# sd_adapter.net
KiCad netlist of a schematic drawn in EAGLE
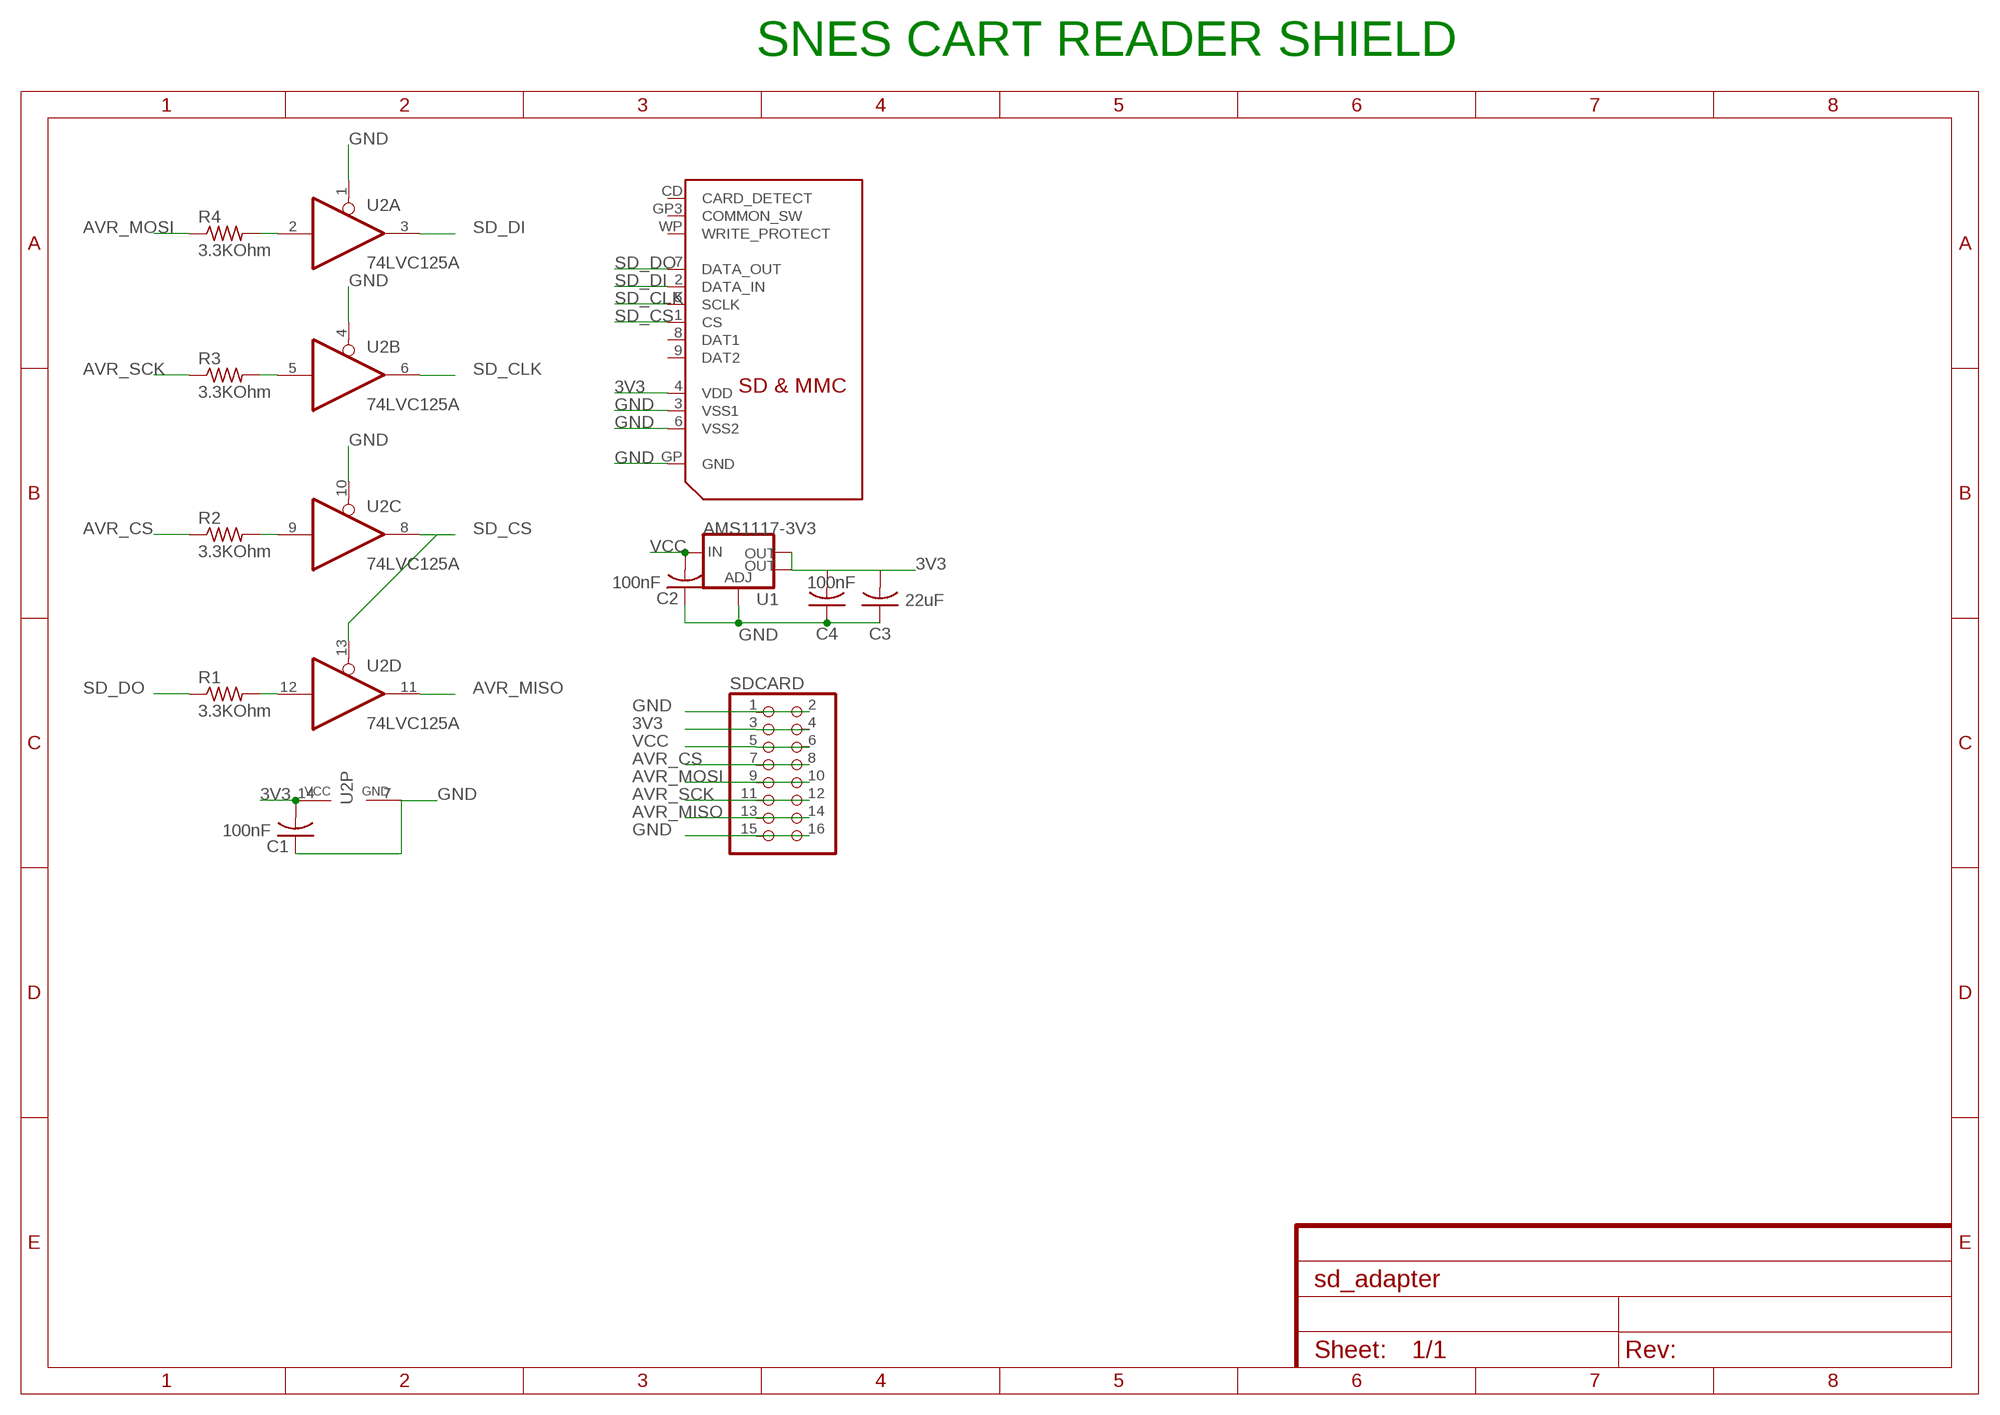
[diagram p0: schematic, sheet 1]

(export (version "E")
  (design (tool "Eeschema 10.0.6"))
  (components
    (comp (ref "C1")
      (value "100nF")
      (footprint "eagle-import:C0805")
      (libsource (lib "eagle-import") (part "C-USC0805"))
    )
    (comp (ref "C2")
      (value "100nF")
      (footprint "eagle-import:C0805")
      (libsource (lib "eagle-import") (part "C-USC0805"))
    )
    (comp (ref "C3")
      (value "22uF")
      (footprint "eagle-import:C0805")
      (libsource (lib "eagle-import") (part "C-USC0805"))
    )
    (comp (ref "C4")
      (value "100nF")
      (footprint "eagle-import:C0805")
      (libsource (lib "eagle-import") (part "C-USC0805"))
    )
    (comp (ref "R1")
      (value "3.3KOhm")
      (footprint "eagle-import:R0805")
      (libsource (lib "eagle-import") (part "R-US_R0805"))
    )
    (comp (ref "R2")
      (value "3.3KOhm")
      (footprint "eagle-import:R0805")
      (libsource (lib "eagle-import") (part "R-US_R0805"))
    )
    (comp (ref "R3")
      (value "3.3KOhm")
      (footprint "eagle-import:R0805")
      (libsource (lib "eagle-import") (part "R-US_R0805"))
    )
    (comp (ref "R4")
      (value "3.3KOhm")
      (footprint "eagle-import:R0805")
      (libsource (lib "eagle-import") (part "R-US_R0805"))
    )
    (comp (ref "SDCARD")
      (value "PINHD-2X8_2.54")
      (footprint "eagle-import:2X08")
      (libsource (lib "eagle-import") (part "PINHD-2X8_2.54"))
    )
    (comp (ref "U$1")
      (value "SDMMC06132")
      (footprint "eagle-import:06132")
      (libsource (lib "eagle-import") (part "SDMMC06132"))
    )
    (comp (ref "U1")
      (value "AMS1117-3V3")
      (footprint "eagle-import:SOT223")
      (libsource (lib "eagle-import") (part "SMD-AMS1117SOT223"))
    )
    (comp (ref "U2")
      (value "74LVC125A")
      (footprint "eagle-import:TSSOP14")
      (libsource (lib "eagle-import") (part "74125PWABT"))
    )
  )
  (nets
    (net (code "1") (name "/3V3") (class "Default")
      (node (ref "C1") (pin "2") (pinfunction "2_2") (pintype "passive"))
      (node (ref "C3") (pin "2") (pinfunction "2_2") (pintype "passive"))
      (node (ref "C4") (pin "2") (pinfunction "2_2") (pintype "passive"))
      (node (ref "SDCARD") (pin "3") (pinfunction "3_3") (pintype "passive"))
      (node (ref "SDCARD") (pin "4") (pinfunction "4_4") (pintype "passive"))
      (node (ref "U$1") (pin "4") (pinfunction "VDD_4") (pintype "power_in"))
      (node (ref "U1") (pin "2") (pinfunction "OUT_2") (pintype "output"))
      (node (ref "U1") (pin "4") (pinfunction "OUT_4") (pintype "output"))
      (node (ref "U2") (pin "14") (pinfunction "VCC_14") (pintype "power_in"))
    )
    (net (code "2") (name "/AVR_CS") (class "Default")
      (node (ref "R2") (pin "1") (pinfunction "1_1") (pintype "passive"))
      (node (ref "SDCARD") (pin "7") (pinfunction "7_7") (pintype "passive"))
      (node (ref "SDCARD") (pin "8") (pinfunction "8_8") (pintype "passive"))
    )
    (net (code "3") (name "/AVR_MISO") (class "Default")
      (node (ref "SDCARD") (pin "13") (pinfunction "13_13") (pintype "passive"))
      (node (ref "SDCARD") (pin "14") (pinfunction "14_14") (pintype "passive"))
      (node (ref "U2") (pin "11") (pinfunction "O_11") (pintype "tri_state"))
    )
    (net (code "4") (name "/AVR_MOSI") (class "Default")
      (node (ref "R4") (pin "1") (pinfunction "1_1") (pintype "passive"))
      (node (ref "SDCARD") (pin "10") (pinfunction "10_10") (pintype "passive"))
      (node (ref "SDCARD") (pin "9") (pinfunction "9_9") (pintype "passive"))
    )
    (net (code "5") (name "/AVR_SCK") (class "Default")
      (node (ref "R3") (pin "1") (pinfunction "1_1") (pintype "passive"))
      (node (ref "SDCARD") (pin "11") (pinfunction "11_11") (pintype "passive"))
      (node (ref "SDCARD") (pin "12") (pinfunction "12_12") (pintype "passive"))
    )
    (net (code "6") (name "/GND") (class "Default")
      (node (ref "C1") (pin "1") (pinfunction "1_1") (pintype "passive"))
      (node (ref "C2") (pin "1") (pinfunction "1_1") (pintype "passive"))
      (node (ref "C3") (pin "1") (pinfunction "1_1") (pintype "passive"))
      (node (ref "C4") (pin "1") (pinfunction "1_1") (pintype "passive"))
      (node (ref "SDCARD") (pin "1") (pinfunction "1_1") (pintype "passive"))
      (node (ref "SDCARD") (pin "15") (pinfunction "15_15") (pintype "passive"))
      (node (ref "SDCARD") (pin "16") (pinfunction "16_16") (pintype "passive"))
      (node (ref "SDCARD") (pin "2") (pinfunction "2_2") (pintype "passive"))
      (node (ref "U$1") (pin "3") (pinfunction "VSS1_3") (pintype "power_in"))
      (node (ref "U$1") (pin "6") (pinfunction "VSS2_6") (pintype "power_in"))
      (node (ref "U$1") (pin "GP") (pinfunction "GND_GP") (pintype "power_in"))
      (node (ref "U1") (pin "1") (pinfunction "ADJ_1") (pintype "input"))
      (node (ref "U2") (pin "1") (pinfunction "OE_1") (pintype "input"))
      (node (ref "U2") (pin "10") (pinfunction "OE_10") (pintype "input"))
      (node (ref "U2") (pin "4") (pinfunction "OE_4") (pintype "input"))
      (node (ref "U2") (pin "7") (pinfunction "GND_7") (pintype "power_in"))
    )
    (net (code "7") (name "/SD_CLK") (class "Default")
      (node (ref "U$1") (pin "5") (pinfunction "SCLK_5") (pintype "input"))
      (node (ref "U2") (pin "6") (pinfunction "O_6") (pintype "tri_state"))
    )
    (net (code "8") (name "/SD_CS") (class "Default")
      (node (ref "U$1") (pin "1") (pinfunction "CS_1") (pintype "input"))
      (node (ref "U2") (pin "13") (pinfunction "OE_13") (pintype "input"))
      (node (ref "U2") (pin "8") (pinfunction "O_8") (pintype "tri_state"))
    )
    (net (code "9") (name "/SD_DI") (class "Default")
      (node (ref "U$1") (pin "2") (pinfunction "DATA_IN_2") (pintype "input"))
      (node (ref "U2") (pin "3") (pinfunction "O_3") (pintype "tri_state"))
    )
    (net (code "10") (name "/SD_DO") (class "Default")
      (node (ref "R1") (pin "1") (pinfunction "1_1") (pintype "passive"))
      (node (ref "U$1") (pin "7") (pinfunction "DATA_OUT_7") (pintype "output"))
    )
    (net (code "11") (name "/VCC") (class "Default")
      (node (ref "C2") (pin "2") (pinfunction "2_2") (pintype "passive"))
      (node (ref "SDCARD") (pin "5") (pinfunction "5_5") (pintype "passive"))
      (node (ref "SDCARD") (pin "6") (pinfunction "6_6") (pintype "passive"))
      (node (ref "U1") (pin "3") (pinfunction "IN_3") (pintype "input"))
    )
    (net (code "12") (name "Net-(U2A-I)") (class "Default")
      (node (ref "R4") (pin "2") (pinfunction "2_2") (pintype "passive"))
      (node (ref "U2") (pin "2") (pinfunction "I_2") (pintype "input"))
    )
    (net (code "13") (name "Net-(U2B-I)") (class "Default")
      (node (ref "R3") (pin "2") (pinfunction "2_2") (pintype "passive"))
      (node (ref "U2") (pin "5") (pinfunction "I_5") (pintype "input"))
    )
    (net (code "14") (name "Net-(U2C-I)") (class "Default")
      (node (ref "R2") (pin "2") (pinfunction "2_2") (pintype "passive"))
      (node (ref "U2") (pin "9") (pinfunction "I_9") (pintype "input"))
    )
    (net (code "15") (name "Net-(U2D-I)") (class "Default")
      (node (ref "R1") (pin "2") (pinfunction "2_2") (pintype "passive"))
      (node (ref "U2") (pin "12") (pinfunction "I_12") (pintype "input"))
    )
    (net (code "16") (name "unconnected-(U$1-CARD_DETECT-PadCD)") (class "Default")
      (node (ref "U$1") (pin "CD") (pinfunction "CARD_DETECT_CD") (pintype "passive"))
    )
    (net (code "17") (name "unconnected-(U$1-COMMON_SW-PadGP3)") (class "Default")
      (node (ref "U$1") (pin "GP3") (pinfunction "COMMON_SW_GP3") (pintype "passive"))
    )
    (net (code "18") (name "unconnected-(U$1-DAT1-Pad8)") (class "Default")
      (node (ref "U$1") (pin "8") (pinfunction "DAT1_8") (pintype "bidirectional"))
    )
    (net (code "19") (name "unconnected-(U$1-DAT2-Pad9)") (class "Default")
      (node (ref "U$1") (pin "9") (pinfunction "DAT2_9") (pintype "bidirectional"))
    )
    (net (code "20") (name "unconnected-(U$1-WRITE_PROTECT-PadWP)") (class "Default")
      (node (ref "U$1") (pin "WP") (pinfunction "WRITE_PROTECT_WP") (pintype "passive"))
    )
  )
)
